# SCHW.net
KiCad netlist of a schematic drawn in EAGLE
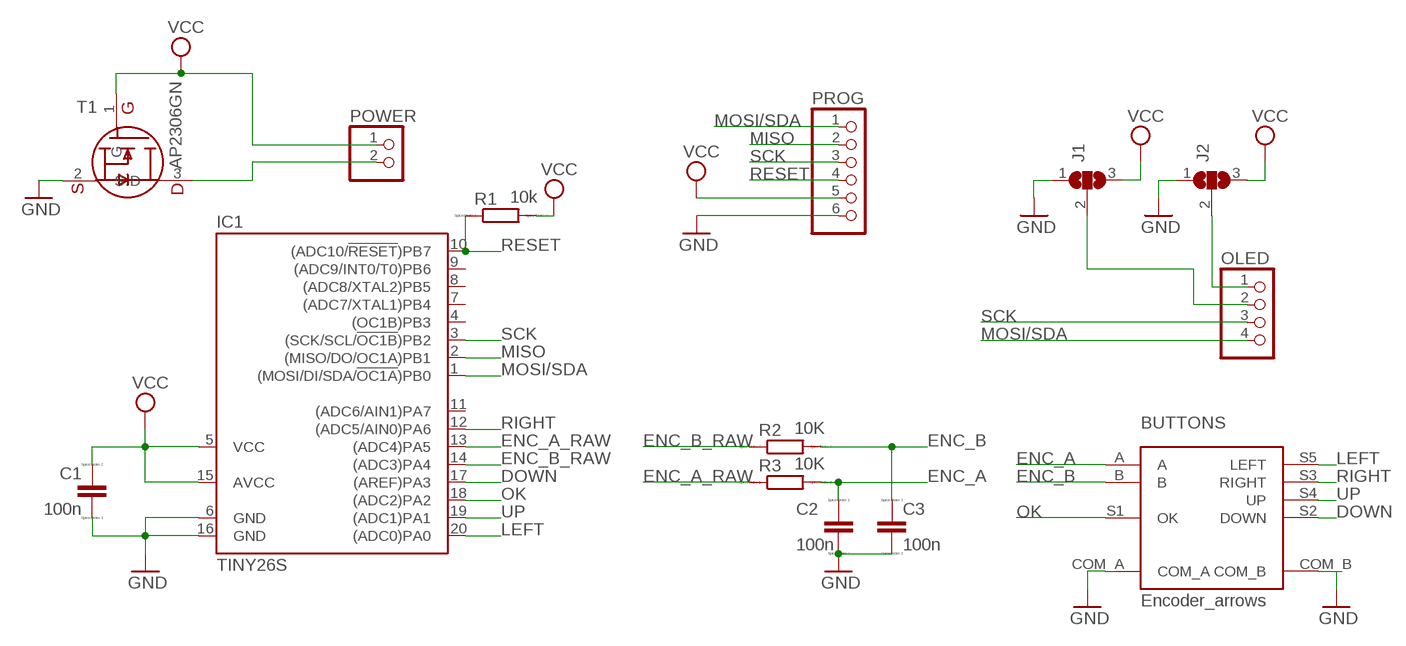
[diagram p0: schematic, sheet 1]

(export (version "E")
  (design (tool "Eeschema 10.0.6"))
  (components
    (comp (ref "BUTTONS")
      (value "ENCODER_ARROWS")
      (footprint "eagle-import:ENCODER_ARROWS")
      (libsource (lib "eagle-import") (part "ENCODER_ARROWS"))
    )
    (comp (ref "C1")
      (value "100n")
      (footprint "eagle-import:C0805")
      (libsource (lib "eagle-import") (part "C"))
    )
    (comp (ref "C2")
      (value "100n")
      (footprint "eagle-import:C0805")
      (libsource (lib "eagle-import") (part "C"))
    )
    (comp (ref "C3")
      (value "100n")
      (footprint "eagle-import:C0805")
      (libsource (lib "eagle-import") (part "C"))
    )
    (comp (ref "IC1")
      (value "TINY26S")
      (footprint "eagle-import:SO20L")
      (fields (field (name "MPN") "ATTINY261-20SU"))
      (libsource (lib "eagle-import") (part "TINY26S"))
    )
    (comp (ref "J1")
      (value "SJ2W")
      (footprint "eagle-import:SJ_2")
      (libsource (lib "eagle-import") (part "SJ2W"))
    )
    (comp (ref "J2")
      (value "SJ2W")
      (footprint "eagle-import:SJ_2")
      (libsource (lib "eagle-import") (part "SJ2W"))
    )
    (comp (ref "OLED")
      (value "PINHD-1X4")
      (footprint "eagle-import:1X04")
      (libsource (lib "eagle-import") (part "PINHD-1X4"))
    )
    (comp (ref "POWER")
      (value "PINHD-1X2")
      (footprint "eagle-import:1X02")
      (libsource (lib "eagle-import") (part "PINHD-1X2"))
    )
    (comp (ref "PROG")
      (value "PINHD-1X6")
      (footprint "eagle-import:1X06")
      (libsource (lib "eagle-import") (part "PINHD-1X6"))
    )
    (comp (ref "R1")
      (value "10k")
      (footprint "eagle-import:R0805")
      (libsource (lib "eagle-import") (part "R"))
    )
    (comp (ref "R2")
      (value "10K")
      (footprint "eagle-import:R0805")
      (libsource (lib "eagle-import") (part "R"))
    )
    (comp (ref "R3")
      (value "10K")
      (footprint "eagle-import:R0805")
      (libsource (lib "eagle-import") (part "R"))
    )
    (comp (ref "T1")
      (value "AP2306GN_MOSFETSOT23")
      (footprint "eagle-import:SOT23")
      (libsource (lib "eagle-import") (part "AP2306GN_MOSFETSOT23"))
    )
  )
  (nets
    (net (code "1") (name "DOWN") (class "Default")
      (node (ref "BUTTONS") (pin "S2") (pinfunction "DOWN_S2") (pintype "bidirectional"))
      (node (ref "IC1") (pin "17") (pinfunction "(AREF)PA3_17") (pintype "bidirectional"))
    )
    (net (code "2") (name "ENC_A") (class "Default")
      (node (ref "BUTTONS") (pin "A") (pinfunction "A_A") (pintype "bidirectional"))
      (node (ref "C2") (pin "1") (pinfunction "1_1") (pintype "passive"))
      (node (ref "R3") (pin "2") (pinfunction "2_2") (pintype "passive"))
    )
    (net (code "3") (name "ENC_A_RAW") (class "Default")
      (node (ref "IC1") (pin "13") (pinfunction "(ADC4)PA5_13") (pintype "bidirectional"))
      (node (ref "R3") (pin "1") (pinfunction "1_1") (pintype "passive"))
    )
    (net (code "4") (name "ENC_B") (class "Default")
      (node (ref "BUTTONS") (pin "B") (pinfunction "B_B") (pintype "bidirectional"))
      (node (ref "C3") (pin "1") (pinfunction "1_1") (pintype "passive"))
      (node (ref "R2") (pin "2") (pinfunction "2_2") (pintype "passive"))
    )
    (net (code "5") (name "ENC_B_RAW") (class "Default")
      (node (ref "IC1") (pin "14") (pinfunction "(ADC3)PA4_14") (pintype "bidirectional"))
      (node (ref "R2") (pin "1") (pinfunction "1_1") (pintype "passive"))
    )
    (net (code "6") (name "GND") (class "Default")
      (node (ref "BUTTONS") (pin "COM_A") (pinfunction "COM_A_COM_A") (pintype "bidirectional"))
      (node (ref "BUTTONS") (pin "COM_B") (pinfunction "COM_B_COM_B") (pintype "bidirectional"))
      (node (ref "C1") (pin "1") (pinfunction "1_1") (pintype "passive"))
      (node (ref "C2") (pin "2") (pinfunction "2_2") (pintype "passive"))
      (node (ref "C3") (pin "2") (pinfunction "2_2") (pintype "passive"))
      (node (ref "IC1") (pin "16") (pinfunction "GND_16") (pintype "power_in"))
      (node (ref "IC1") (pin "6") (pinfunction "GND_6") (pintype "power_in"))
      (node (ref "J1") (pin "1") (pinfunction "1_1") (pintype "passive"))
      (node (ref "J2") (pin "1") (pinfunction "1_1") (pintype "passive"))
      (node (ref "PROG") (pin "6") (pinfunction "6_6") (pintype "passive"))
      (node (ref "T1") (pin "2") (pinfunction "S_2") (pintype "bidirectional"))
    )
    (net (code "7") (name "LEFT") (class "Default")
      (node (ref "BUTTONS") (pin "S5") (pinfunction "LEFT_S5") (pintype "bidirectional"))
      (node (ref "IC1") (pin "20") (pinfunction "(ADC0)PA0_20") (pintype "bidirectional"))
    )
    (net (code "8") (name "MISO") (class "Default")
      (node (ref "IC1") (pin "2") (pinfunction "(MISO/DO/OC1A)PB1_2") (pintype "bidirectional"))
      (node (ref "PROG") (pin "2") (pinfunction "2_2") (pintype "passive"))
    )
    (net (code "9") (name "MOSI{slash}SDA") (class "Default")
      (node (ref "IC1") (pin "1") (pinfunction "(MOSI/DI/SDA/~{OC1A})PB0_1") (pintype "bidirectional"))
      (node (ref "OLED") (pin "4") (pinfunction "4_4") (pintype "passive"))
      (node (ref "PROG") (pin "1") (pinfunction "1_1") (pintype "passive"))
    )
    (net (code "10") (name "Net-(J1-Pad2)") (class "Default")
      (node (ref "J1") (pin "2") (pinfunction "2_2") (pintype "passive"))
      (node (ref "OLED") (pin "2") (pinfunction "2_2") (pintype "passive"))
    )
    (net (code "11") (name "Net-(J2-Pad2)") (class "Default")
      (node (ref "J2") (pin "2") (pinfunction "2_2") (pintype "passive"))
      (node (ref "OLED") (pin "1") (pinfunction "1_1") (pintype "passive"))
    )
    (net (code "12") (name "Net-(T1-D)") (class "Default")
      (node (ref "POWER") (pin "2") (pinfunction "2_2") (pintype "passive"))
      (node (ref "T1") (pin "3") (pinfunction "D_3") (pintype "bidirectional"))
    )
    (net (code "13") (name "OK") (class "Default")
      (node (ref "BUTTONS") (pin "S1") (pinfunction "OK_S1") (pintype "bidirectional"))
      (node (ref "IC1") (pin "18") (pinfunction "(ADC2)PA2_18") (pintype "bidirectional"))
    )
    (net (code "14") (name "RESET") (class "Default")
      (node (ref "IC1") (pin "10") (pinfunction "(ADC10/~{RESET})PB7_10") (pintype "bidirectional"))
      (node (ref "PROG") (pin "4") (pinfunction "4_4") (pintype "passive"))
      (node (ref "R1") (pin "1") (pinfunction "1_1") (pintype "passive"))
    )
    (net (code "15") (name "RIGHT") (class "Default")
      (node (ref "BUTTONS") (pin "S3") (pinfunction "RIGHT_S3") (pintype "bidirectional"))
      (node (ref "IC1") (pin "12") (pinfunction "(ADC5/AIN0)PA6_12") (pintype "bidirectional"))
    )
    (net (code "16") (name "SCK") (class "Default")
      (node (ref "IC1") (pin "3") (pinfunction "(SCK/SCL/~{OC1B})PB2_3") (pintype "bidirectional"))
      (node (ref "OLED") (pin "3") (pinfunction "3_3") (pintype "passive"))
      (node (ref "PROG") (pin "3") (pinfunction "3_3") (pintype "passive"))
    )
    (net (code "17") (name "UP") (class "Default")
      (node (ref "BUTTONS") (pin "S4") (pinfunction "UP_S4") (pintype "bidirectional"))
      (node (ref "IC1") (pin "19") (pinfunction "(ADC1)PA1_19") (pintype "bidirectional"))
    )
    (net (code "18") (name "VCC") (class "Default")
      (node (ref "C1") (pin "2") (pinfunction "2_2") (pintype "passive"))
      (node (ref "IC1") (pin "15") (pinfunction "AVCC_15") (pintype "power_in"))
      (node (ref "IC1") (pin "5") (pinfunction "VCC_5") (pintype "power_in"))
      (node (ref "J1") (pin "3") (pinfunction "3_3") (pintype "passive"))
      (node (ref "J2") (pin "3") (pinfunction "3_3") (pintype "passive"))
      (node (ref "POWER") (pin "1") (pinfunction "1_1") (pintype "passive"))
      (node (ref "PROG") (pin "5") (pinfunction "5_5") (pintype "passive"))
      (node (ref "R1") (pin "2") (pinfunction "2_2") (pintype "passive"))
      (node (ref "T1") (pin "1") (pinfunction "G_1") (pintype "bidirectional"))
    )
    (net (code "19") (name "unconnected-(IC1-(ADC6{slash}AIN1)PA7-Pad11)") (class "Default")
      (node (ref "IC1") (pin "11") (pinfunction "(ADC6/AIN1)PA7_11") (pintype "bidirectional"))
    )
    (net (code "20") (name "unconnected-(IC1-(ADC7{slash}XTAL1)PB4-Pad7)") (class "Default")
      (node (ref "IC1") (pin "7") (pinfunction "(ADC7/XTAL1)PB4_7") (pintype "bidirectional"))
    )
    (net (code "21") (name "unconnected-(IC1-(ADC8{slash}XTAL2)PB5-Pad8)") (class "Default")
      (node (ref "IC1") (pin "8") (pinfunction "(ADC8/XTAL2)PB5_8") (pintype "bidirectional"))
    )
    (net (code "22") (name "unconnected-(IC1-(ADC9{slash}INT0{slash}T0)PB6-Pad9)") (class "Default")
      (node (ref "IC1") (pin "9") (pinfunction "(ADC9/INT0/T0)PB6_9") (pintype "bidirectional"))
    )
    (net (code "23") (name "unconnected-(IC1-(OC1B)PB3-Pad4)") (class "Default")
      (node (ref "IC1") (pin "4") (pinfunction "(OC1B)PB3_4") (pintype "bidirectional"))
    )
  )
)
